# QS30-HV.net
KiCad netlist of a schematic drawn in Altium Designer
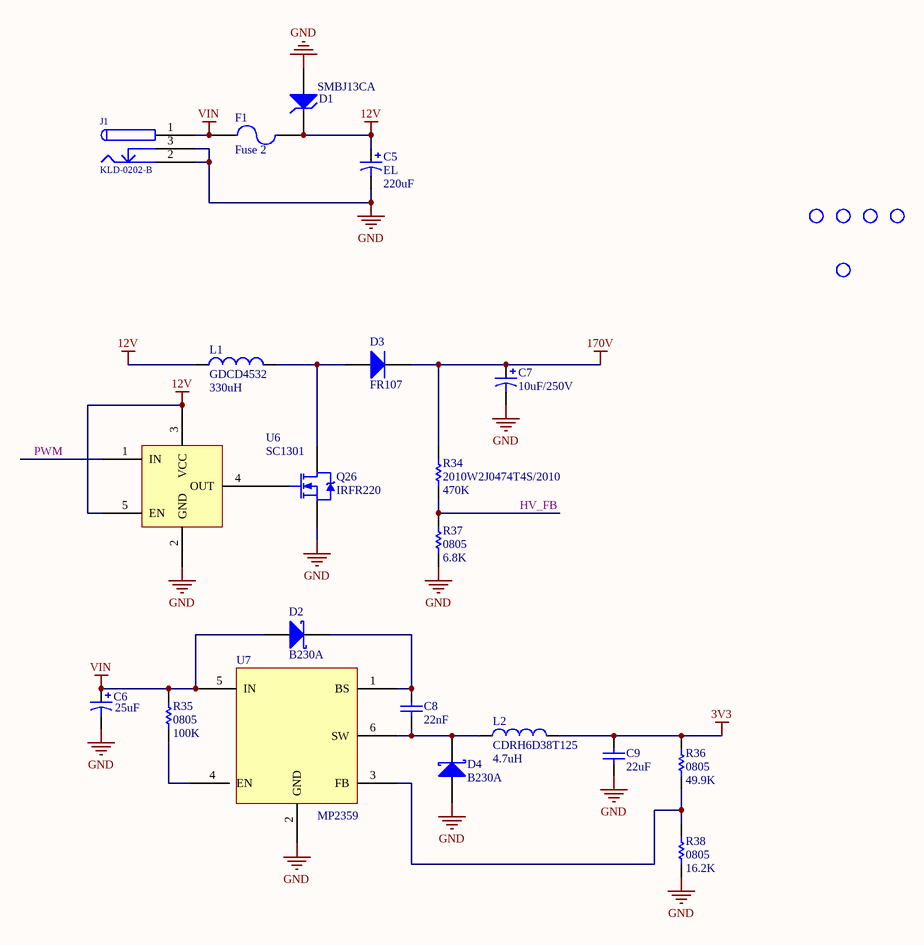
[diagram p0: QS30-HV.SchDoc]

(export (version "E")
  (design (tool "Eeschema 10.0.6"))
  (components
    (comp (ref "C5")
      (value "EL")
      (footprint "220UF_16V_SMD_CAP")
      (description "Polarized Capacitor (Radial)")
      (fields (field (name "ALTIUM_VALUE") "220uF") (field (name "PUBLISHER") "Altium Limited"))
      (libsource (lib "Miscellaneous Devices") (part "Cap Pol1"))
    )
    (comp (ref "C6")
      (value "25uF")
      (footprint "C1210")
      (description "Polarized Capacitor (Radial)")
      (fields (field (name "PUBLISHER") "Altium Limited"))
      (libsource (lib "Miscellaneous Devices") (part "Cap Pol1"))
    )
    (comp (ref "C7")
      (value "10uF/250V")
      (footprint "C10.2 - SMD")
      (description "Polarized Capacitor (Radial)")
      (fields (field (name "Comment") "Cap Pol1") (field (name "PUBLISHER") "Altium Limited"))
      (libsource (lib "Miscellaneous Devices") (part "Cap Pol1"))
    )
    (comp (ref "C8")
      (value "22nF")
      (footprint "6-0805_N")
      (description "Capacitor")
      (fields (field (name "Comment") "Cap") (field (name "PUBLISHER") "Altium Limited"))
      (libsource (lib "Miscellaneous Devices") (part "Cap"))
    )
    (comp (ref "C9")
      (value "22uF")
      (footprint "C1210")
      (description "Capacitor")
      (fields (field (name "Comment") "Cap") (field (name "PUBLISHER") "Altium Limited"))
      (libsource (lib "Miscellaneous Devices") (part "Cap"))
    )
    (comp (ref "D1")
      (value "SMBJ13CA")
      (footprint "SMB")
      (description "Zener Diode")
      (fields (field (name "PUBLISHER") "Altium Limited"))
      (libsource (lib "Miscellaneous Devices") (part "D Zener"))
    )
    (comp (ref "D2")
      (value "B230A")
      (footprint "SOD123")
      (description "Schottky Diode")
      (fields (field (name "PUBLISHER") "Altium Limited"))
      (libsource (lib "Miscellaneous Devices") (part "D Schottky"))
    )
    (comp (ref "D3")
      (value "FR107")
      (footprint "DSO-C2/X1.8")
      (description "High Conductance Fast Diode")
      (fields (field (name "PUBLISHER") "Altium Limited"))
      (libsource (lib "Miscellaneous Devices") (part "Diode 1N914"))
    )
    (comp (ref "D4")
      (value "B230A")
      (footprint "SOD123")
      (description "Schottky Diode")
      (fields (field (name "PUBLISHER") "Altium Limited"))
      (libsource (lib "Miscellaneous Devices") (part "D Schottky"))
    )
    (comp (ref "F1")
      (value "Fuse 2")
      (footprint "1812")
      (description "Fuse")
      (fields (field (name "PUBLISHER") "Altium Limited"))
      (libsource (lib "Miscellaneous Devices") (part "Fuse 2"))
    )
    (comp (ref "g1") (value "g固定过孔") (footprint "固定过孔") (libsource (lib "常用封装库") (part "g固定过孔")))
    (comp (ref "g2") (value "g固定过孔") (footprint "固定过孔") (libsource (lib "常用封装库") (part "g固定过孔")))
    (comp (ref "g3") (value "g固定过孔") (footprint "固定过孔") (libsource (lib "常用封装库") (part "g固定过孔")))
    (comp (ref "g4") (value "g固定过孔") (footprint "固定过孔") (libsource (lib "常用封装库") (part "g固定过孔")))
    (comp (ref "g6")
      (value "g固定过孔")
      (footprint "PCBComponent_1 - duplicate3")
      (libsource (lib "常用封装库") (part "g固定过孔"))
    )
    (comp (ref "J1")
      (value "KLD-0202-B")
      (footprint "DC_JACK_SMT_4.0_1.7")
      (description "Low Voltage Power Supply Connector")
      (fields (field (name "MANUFACTURER") "Kycon"))
      (libsource (lib "SpiritLevel_2E") (part "KLD-0202-B"))
    )
    (comp (ref "L1")
      (value "GDCD4532")
      (footprint "GDCD4532")
      (description "Inductor")
      (fields (field (name "ALTIUM_VALUE") "330uH") (field (name "PUBLISHER") "Altium Limited"))
      (libsource (lib "Miscellaneous Devices") (part "Inductor"))
    )
    (comp (ref "L2")
      (value "CDRH6D38T125")
      (footprint "GDCD4532")
      (description "Inductor")
      (fields (field (name "ALTIUM_VALUE") "4.7uH") (field (name "PUBLISHER") "Altium Limited"))
      (libsource (lib "Miscellaneous Devices") (part "Inductor"))
    )
    (comp (ref "Q26")
      (value "IRFR220")
      (footprint "TO-252AA_N")
      (description "HEXFET Power MOSFET")
      (fields (field (name "PUBLISHER") "Altium Limited"))
      (libsource (lib "IR Discrete MOSFET - Power") (part "IRFR220"))
    )
    (comp (ref "R34")
      (value "2010W2J0474T4S/2010")
      (footprint "12Z-2010")
      (description "Resistor")
      (fields (field (name "ALTIUM_VALUE") "470K") (field (name "PUBLISHER") "Altium Limited"))
      (libsource (lib "Miscellaneous Devices") (part "Res1"))
    )
    (comp (ref "R35")
      (value "0805")
      (footprint "1608[0603]")
      (description "Resistor")
      (fields (field (name "ALTIUM_VALUE") "100K") (field (name "PUBLISHER") "Altium Limited"))
      (libsource (lib "Miscellaneous Devices") (part "Res1"))
    )
    (comp (ref "R36")
      (value "0805")
      (footprint "6-0805_N")
      (description "Resistor")
      (fields (field (name "ALTIUM_VALUE") "49.9K") (field (name "PUBLISHER") "Altium Limited"))
      (libsource (lib "Miscellaneous Devices") (part "Res1"))
    )
    (comp (ref "R37")
      (value "0805")
      (footprint "6-0805_N")
      (description "Resistor")
      (fields (field (name "ALTIUM_VALUE") "6.8K") (field (name "PUBLISHER") "Altium Limited"))
      (libsource (lib "Miscellaneous Devices") (part "Res1"))
    )
    (comp (ref "R38")
      (value "0805")
      (footprint "6-0805_N")
      (description "Resistor")
      (fields (field (name "ALTIUM_VALUE") "16.2K") (field (name "PUBLISHER") "Altium Limited"))
      (libsource (lib "Miscellaneous Devices") (part "Res1"))
    )
    (comp (ref "U6") (value "SC1301") (footprint "SOT23-5_L") (libsource (lib "常用封装库") (part "SC1301")))
    (comp (ref "U7") (value "MP2359") (footprint "SOT-23_A") (libsource (lib "NEW") (part "MP2359")))
  )
  (nets
    (net (code "1") (name "/HV_FB") (class "Default")
      (node (ref "R34") (pin "1") (pinfunction "1_1") (pintype "passive"))
      (node (ref "R37") (pin "2") (pinfunction "2_2") (pintype "passive"))
    )
    (net (code "2") (name "/PWM") (class "Default")
      (node (ref "U6") (pin "1") (pinfunction "IN_1") (pintype "passive"))
    )
    (net (code "3") (name "3V3") (class "Default")
      (node (ref "C9") (pin "2") (pinfunction "2_2") (pintype "passive"))
      (node (ref "L2") (pin "2") (pinfunction "2_2") (pintype "passive"))
      (node (ref "R36") (pin "2") (pinfunction "2_2") (pintype "passive"))
    )
    (net (code "4") (name "12V") (class "Default")
      (node (ref "C5") (pin "1") (pinfunction "1_1") (pintype "passive"))
      (node (ref "D1") (pin "2") (pinfunction "K_2") (pintype "passive"))
      (node (ref "F1") (pin "2") (pinfunction "2_2") (pintype "passive"))
      (node (ref "L1") (pin "1") (pinfunction "1_1") (pintype "passive"))
      (node (ref "U6") (pin "3") (pinfunction "VCC_3") (pintype "passive"))
      (node (ref "U6") (pin "5") (pinfunction "EN_5") (pintype "passive"))
    )
    (net (code "5") (name "170V") (class "Default")
      (node (ref "C7") (pin "1") (pinfunction "1_1") (pintype "passive"))
      (node (ref "D3") (pin "2") (pinfunction "K_2") (pintype "passive"))
      (node (ref "R34") (pin "2") (pinfunction "2_2") (pintype "passive"))
    )
    (net (code "6") (name "GND") (class "Default")
      (node (ref "C5") (pin "2") (pinfunction "2_2") (pintype "passive"))
      (node (ref "C6") (pin "2") (pinfunction "2_2") (pintype "passive"))
      (node (ref "C7") (pin "2") (pinfunction "2_2") (pintype "passive"))
      (node (ref "C9") (pin "1") (pinfunction "1_1") (pintype "passive"))
      (node (ref "D1") (pin "1") (pinfunction "A_1") (pintype "passive"))
      (node (ref "D4") (pin "1") (pinfunction "A_1") (pintype "passive"))
      (node (ref "J1") (pin "2") (pintype "power_in"))
      (node (ref "J1") (pin "3") (pintype "power_in"))
      (node (ref "Q26") (pin "3") (pinfunction "S_3") (pintype "passive"))
      (node (ref "R37") (pin "1") (pinfunction "1_1") (pintype "passive"))
      (node (ref "R38") (pin "1") (pinfunction "1_1") (pintype "passive"))
      (node (ref "U6") (pin "2") (pinfunction "GND_2") (pintype "passive"))
      (node (ref "U7") (pin "2") (pinfunction "GND_2") (pintype "passive"))
    )
    (net (code "7") (name "Net-(D2-K)") (class "Default")
      (node (ref "C8") (pin "2") (pinfunction "2_2") (pintype "passive"))
      (node (ref "D2") (pin "2") (pinfunction "K_2") (pintype "passive"))
      (node (ref "U7") (pin "1") (pinfunction "BS_1") (pintype "passive"))
    )
    (net (code "8") (name "Net-(D3-A)") (class "Default")
      (node (ref "D3") (pin "1") (pinfunction "A_1") (pintype "passive"))
      (node (ref "L1") (pin "2") (pinfunction "2_2") (pintype "passive"))
      (node (ref "Q26") (pin "4") (pinfunction "D_4") (pintype "passive"))
    )
    (net (code "9") (name "Net-(D4-K)") (class "Default")
      (node (ref "C8") (pin "1") (pinfunction "1_1") (pintype "passive"))
      (node (ref "D4") (pin "2") (pinfunction "K_2") (pintype "passive"))
      (node (ref "L2") (pin "1") (pinfunction "1_1") (pintype "passive"))
      (node (ref "U7") (pin "6") (pinfunction "SW_6") (pintype "passive"))
    )
    (net (code "10") (name "Net-(Q26-G)") (class "Default")
      (node (ref "Q26") (pin "1") (pinfunction "G_1") (pintype "passive"))
      (node (ref "U6") (pin "4") (pinfunction "OUT_4") (pintype "passive"))
    )
    (net (code "11") (name "Net-(U7-EN)") (class "Default")
      (node (ref "R35") (pin "1") (pinfunction "1_1") (pintype "passive"))
      (node (ref "U7") (pin "4") (pinfunction "EN_4") (pintype "passive"))
    )
    (net (code "12") (name "Net-(U7-FB)") (class "Default")
      (node (ref "R36") (pin "1") (pinfunction "1_1") (pintype "passive"))
      (node (ref "R38") (pin "2") (pinfunction "2_2") (pintype "passive"))
      (node (ref "U7") (pin "3") (pinfunction "FB_3") (pintype "passive"))
    )
    (net (code "13") (name "VIN") (class "Default")
      (node (ref "C6") (pin "1") (pinfunction "1_1") (pintype "passive"))
      (node (ref "D2") (pin "1") (pinfunction "A_1") (pintype "passive"))
      (node (ref "F1") (pin "1") (pinfunction "1_1") (pintype "passive"))
      (node (ref "J1") (pin "1") (pintype "power_in"))
      (node (ref "R35") (pin "2") (pinfunction "2_2") (pintype "passive"))
      (node (ref "U7") (pin "5") (pinfunction "IN_5") (pintype "passive"))
    )
  )
)
